# mpc56_mcupower.net
KiCad netlist of a schematic drawn in Altium Designer
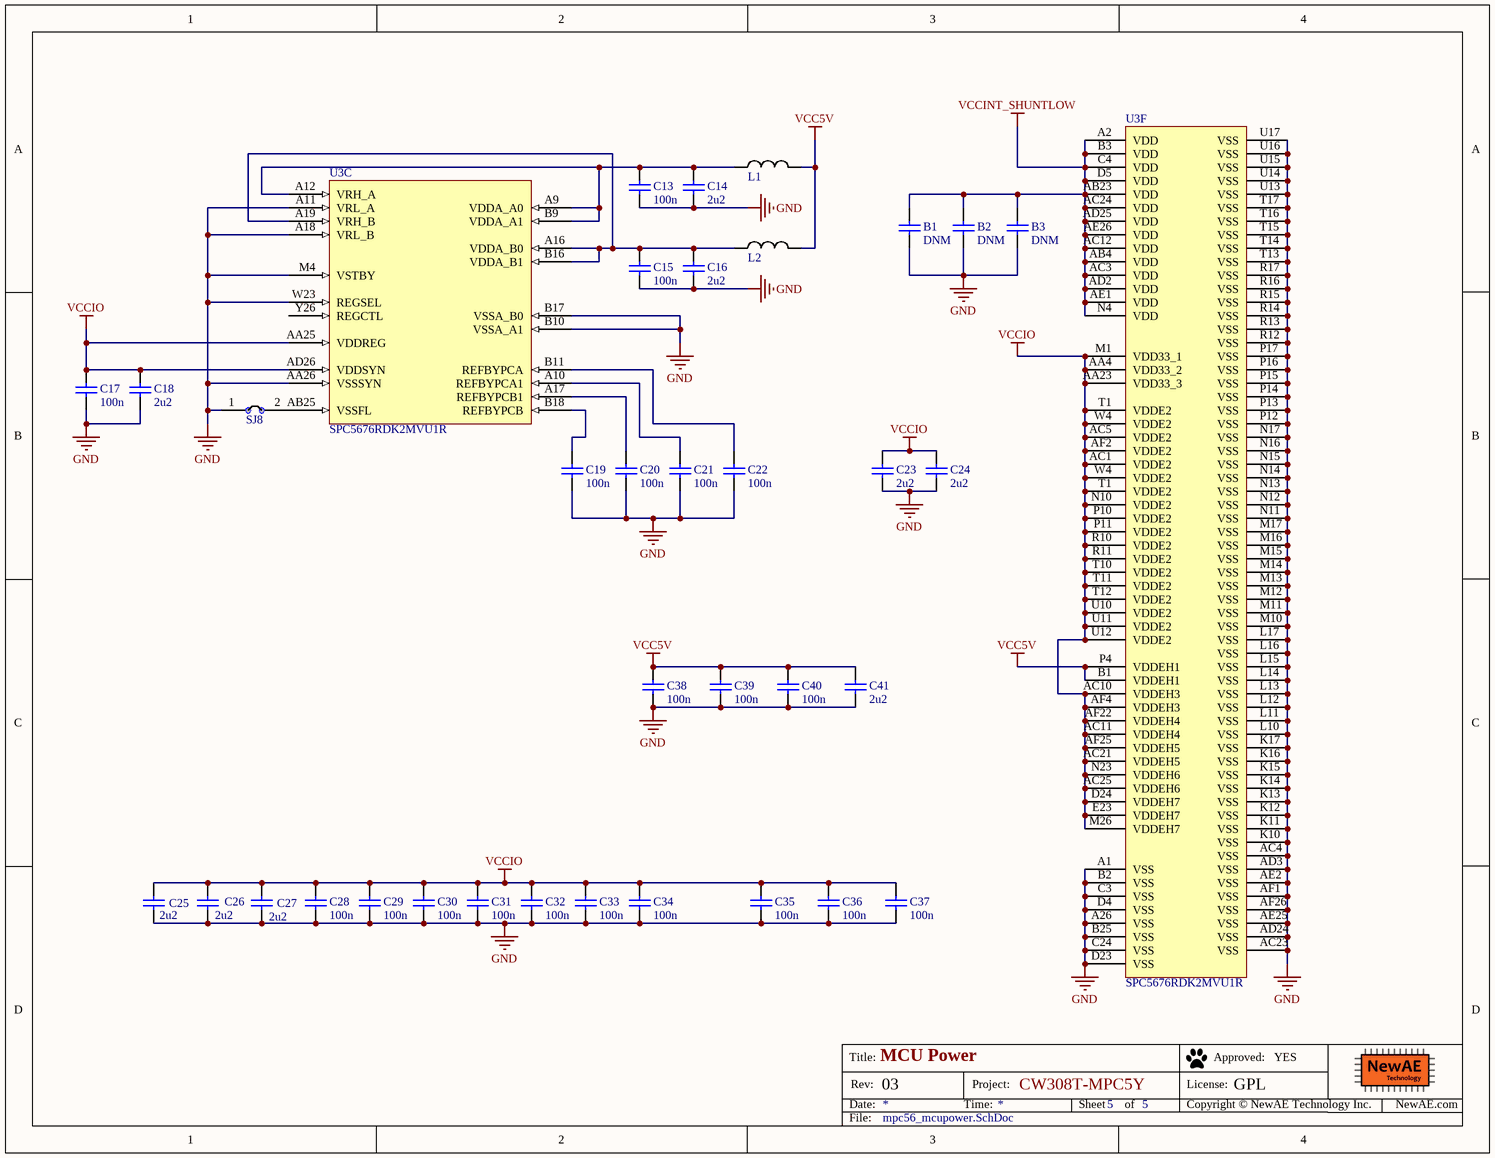
[diagram p0: mpc56_mcupower.SchDoc]

(export (version "E")
  (design (tool "Eeschema 10.0.6"))
  (components
    (comp (ref "B1")
      (value "DNM")
      (footprint "CAPC0402_M")
      (description "DNM, 0402")
      (fields (field (name "PART NUMBER") "CCHIP-DNM-0402"))
      (libsource (lib "NewAE_AltiumLib") (part "CAP"))
    )
    (comp (ref "B2")
      (value "DNM")
      (footprint "CAPC0402_M")
      (description "DNM, 0402")
      (fields (field (name "PART NUMBER") "CCHIP-DNM-0402"))
      (libsource (lib "NewAE_AltiumLib") (part "CAP"))
    )
    (comp (ref "B3")
      (value "DNM")
      (footprint "CAPC0402_M")
      (description "DNM, 0402")
      (fields (field (name "PART NUMBER") "CCHIP-DNM-0402"))
      (libsource (lib "NewAE_AltiumLib") (part "CAP"))
    )
    (comp (ref "C13")
      (value "100n")
      (footprint "CAPC0402_M")
      (description "100n, 0402")
      (fields (field (name "PART NUMBER") "CCHIP-100n-0402"))
      (libsource (lib "NewAE_AltiumLib") (part "CAP"))
    )
    (comp (ref "C14")
      (value "2u2")
      (footprint "CAPC0603_M")
      (description "2u2, 0603")
      (fields (field (name "PART NUMBER") "CCHIP-2u2-0603"))
      (libsource (lib "NewAE_AltiumLib") (part "CAP"))
    )
    (comp (ref "C15")
      (value "100n")
      (footprint "CAPC0402_M")
      (description "100n, 0402")
      (fields (field (name "PART NUMBER") "CCHIP-100n-0402"))
      (libsource (lib "NewAE_AltiumLib") (part "CAP"))
    )
    (comp (ref "C16")
      (value "2u2")
      (footprint "CAPC0603_M")
      (description "2u2, 0603")
      (fields (field (name "PART NUMBER") "CCHIP-2u2-0603"))
      (libsource (lib "NewAE_AltiumLib") (part "CAP"))
    )
    (comp (ref "C17")
      (value "100n")
      (footprint "CAPC0402_M")
      (description "100n, 0402")
      (fields (field (name "PART NUMBER") "CCHIP-100n-0402"))
      (libsource (lib "NewAE_AltiumLib") (part "CAP"))
    )
    (comp (ref "C18")
      (value "2u2")
      (footprint "CAPC0603_M")
      (description "2u2, 0603")
      (fields (field (name "PART NUMBER") "CCHIP-2u2-0603"))
      (libsource (lib "NewAE_AltiumLib") (part "CAP"))
    )
    (comp (ref "C19")
      (value "100n")
      (footprint "CAPC0402_M")
      (description "100n, 0402")
      (fields (field (name "PART NUMBER") "CCHIP-100n-0402"))
      (libsource (lib "NewAE_AltiumLib") (part "CAP"))
    )
    (comp (ref "C20")
      (value "100n")
      (footprint "CAPC0402_M")
      (description "100n, 0402")
      (fields (field (name "PART NUMBER") "CCHIP-100n-0402"))
      (libsource (lib "NewAE_AltiumLib") (part "CAP"))
    )
    (comp (ref "C21")
      (value "100n")
      (footprint "CAPC0402_M")
      (description "100n, 0402")
      (fields (field (name "PART NUMBER") "CCHIP-100n-0402"))
      (libsource (lib "NewAE_AltiumLib") (part "CAP"))
    )
    (comp (ref "C22")
      (value "100n")
      (footprint "CAPC0402_M")
      (description "100n, 0402")
      (fields (field (name "PART NUMBER") "CCHIP-100n-0402"))
      (libsource (lib "NewAE_AltiumLib") (part "CAP"))
    )
    (comp (ref "C23")
      (value "2u2")
      (footprint "CAPC0603_M")
      (description "2u2, 0603")
      (fields (field (name "PART NUMBER") "CCHIP-2u2-0603"))
      (libsource (lib "NewAE_AltiumLib") (part "CAP"))
    )
    (comp (ref "C24")
      (value "2u2")
      (footprint "CAPC0603_M")
      (description "2u2, 0603")
      (fields (field (name "PART NUMBER") "CCHIP-2u2-0603"))
      (libsource (lib "NewAE_AltiumLib") (part "CAP"))
    )
    (comp (ref "C25")
      (value "2u2")
      (footprint "CAPC0603_M")
      (description "2u2, 0603")
      (fields (field (name "PART NUMBER") "CCHIP-2u2-0603"))
      (libsource (lib "NewAE_AltiumLib") (part "CAP"))
    )
    (comp (ref "C26")
      (value "2u2")
      (footprint "CAPC0603_M")
      (description "2u2, 0603")
      (fields (field (name "PART NUMBER") "CCHIP-2u2-0603"))
      (libsource (lib "NewAE_AltiumLib") (part "CAP"))
    )
    (comp (ref "C27")
      (value "2u2")
      (footprint "CAPC0603_M")
      (description "2u2, 0603")
      (fields (field (name "PART NUMBER") "CCHIP-2u2-0603"))
      (libsource (lib "NewAE_AltiumLib") (part "CAP"))
    )
    (comp (ref "C28")
      (value "100n")
      (footprint "CAPC0402_M")
      (description "100n, 0402")
      (fields (field (name "PART NUMBER") "CCHIP-100n-0402"))
      (libsource (lib "NewAE_AltiumLib") (part "CAP"))
    )
    (comp (ref "C29")
      (value "100n")
      (footprint "CAPC0402_M")
      (description "100n, 0402")
      (fields (field (name "PART NUMBER") "CCHIP-100n-0402"))
      (libsource (lib "NewAE_AltiumLib") (part "CAP"))
    )
    (comp (ref "C30")
      (value "100n")
      (footprint "CAPC0402_M")
      (description "100n, 0402")
      (fields (field (name "PART NUMBER") "CCHIP-100n-0402"))
      (libsource (lib "NewAE_AltiumLib") (part "CAP"))
    )
    (comp (ref "C31")
      (value "100n")
      (footprint "CAPC0402_M")
      (description "100n, 0402")
      (fields (field (name "PART NUMBER") "CCHIP-100n-0402"))
      (libsource (lib "NewAE_AltiumLib") (part "CAP"))
    )
    (comp (ref "C32")
      (value "100n")
      (footprint "CAPC0402_M")
      (description "100n, 0402")
      (fields (field (name "PART NUMBER") "CCHIP-100n-0402"))
      (libsource (lib "NewAE_AltiumLib") (part "CAP"))
    )
    (comp (ref "C33")
      (value "100n")
      (footprint "CAPC0402_M")
      (description "100n, 0402")
      (fields (field (name "PART NUMBER") "CCHIP-100n-0402"))
      (libsource (lib "NewAE_AltiumLib") (part "CAP"))
    )
    (comp (ref "C34")
      (value "100n")
      (footprint "CAPC0402_M")
      (description "100n, 0402")
      (fields (field (name "PART NUMBER") "CCHIP-100n-0402"))
      (libsource (lib "NewAE_AltiumLib") (part "CAP"))
    )
    (comp (ref "C35")
      (value "100n")
      (footprint "CAPC0402_M")
      (description "100n, 0402")
      (fields (field (name "PART NUMBER") "CCHIP-100n-0402"))
      (libsource (lib "NewAE_AltiumLib") (part "CAP"))
    )
    (comp (ref "C36")
      (value "100n")
      (footprint "CAPC0402_M")
      (description "100n, 0402")
      (fields (field (name "PART NUMBER") "CCHIP-100n-0402"))
      (libsource (lib "NewAE_AltiumLib") (part "CAP"))
    )
    (comp (ref "C37")
      (value "100n")
      (footprint "CAPC0402_M")
      (description "100n, 0402")
      (fields (field (name "PART NUMBER") "CCHIP-100n-0402"))
      (libsource (lib "NewAE_AltiumLib") (part "CAP"))
    )
    (comp (ref "C38")
      (value "100n")
      (footprint "CAPC0402_M")
      (description "100n, 0402")
      (fields (field (name "PART NUMBER") "CCHIP-100n-0402"))
      (libsource (lib "NewAE_AltiumLib") (part "CAP"))
    )
    (comp (ref "C39")
      (value "100n")
      (footprint "CAPC0402_M")
      (description "100n, 0402")
      (fields (field (name "PART NUMBER") "CCHIP-100n-0402"))
      (libsource (lib "NewAE_AltiumLib") (part "CAP"))
    )
    (comp (ref "C40")
      (value "100n")
      (footprint "CAPC0402_M")
      (description "100n, 0402")
      (fields (field (name "PART NUMBER") "CCHIP-100n-0402"))
      (libsource (lib "NewAE_AltiumLib") (part "CAP"))
    )
    (comp (ref "C41")
      (value "2u2")
      (footprint "CAPC0603_M")
      (description "2u2, 0603")
      (fields (field (name "PART NUMBER") "CCHIP-2u2-0603"))
      (libsource (lib "NewAE_AltiumLib") (part "CAP"))
    )
    (comp (ref "L1")
      (value "1k @ 1Mhz")
      (footprint "IND_0603")
      (description "Ferrite Beads HI CUR CHIP BD 0603 1000OHMS 25%")
      (fields (field (name "PART NUMBER") "FBCHIP-1k-0603"))
      (libsource (lib "NewAE_AltiumLib") (part "IND"))
    )
    (comp (ref "L2")
      (value "1k @ 1Mhz")
      (footprint "IND_0603")
      (description "Ferrite Beads HI CUR CHIP BD 0603 1000OHMS 25%")
      (fields (field (name "PART NUMBER") "FBCHIP-1k-0603"))
      (libsource (lib "NewAE_AltiumLib") (part "IND"))
    )
    (comp (ref "SJ8")
      (value "NC")
      (footprint "SJ_2S_NC")
      (description "Solder Jumper, NC")
      (fields (field (name "PART NUMBER") "SJ_2S"))
      (libsource (lib "NewAE_AltiumLib") (part "SJ_2S"))
    )
    (comp (ref "U3")
      (value "SPC5676RDK2MVU1R")
      (footprint "TEPBGA416_27x27")
      (description "Dual-Core PPC, Automotive")
      (libsource (lib "NewAE_AltiumLib") (part "SPC5676RDK2MVU1R"))
    )
  )
  (nets
    (net (code "1") (name "GND") (class "Default")
      (node (ref "B1") (pin "2") (pinfunction "2_2") (pintype "passive"))
      (node (ref "B2") (pin "2") (pinfunction "2_2") (pintype "passive"))
      (node (ref "B3") (pin "2") (pinfunction "2_2") (pintype "passive"))
      (node (ref "C13") (pin "2") (pinfunction "2_2") (pintype "passive"))
      (node (ref "C14") (pin "2") (pinfunction "2_2") (pintype "passive"))
      (node (ref "C15") (pin "2") (pinfunction "2_2") (pintype "passive"))
      (node (ref "C16") (pin "2") (pinfunction "2_2") (pintype "passive"))
      (node (ref "C17") (pin "2") (pinfunction "2_2") (pintype "passive"))
      (node (ref "C18") (pin "2") (pinfunction "2_2") (pintype "passive"))
      (node (ref "C19") (pin "2") (pinfunction "2_2") (pintype "passive"))
      (node (ref "C20") (pin "2") (pinfunction "2_2") (pintype "passive"))
      (node (ref "C21") (pin "2") (pinfunction "2_2") (pintype "passive"))
      (node (ref "C22") (pin "2") (pinfunction "2_2") (pintype "passive"))
      (node (ref "C23") (pin "2") (pinfunction "2_2") (pintype "passive"))
      (node (ref "C24") (pin "2") (pinfunction "2_2") (pintype "passive"))
      (node (ref "C25") (pin "2") (pinfunction "2_2") (pintype "passive"))
      (node (ref "C26") (pin "2") (pinfunction "2_2") (pintype "passive"))
      (node (ref "C27") (pin "2") (pinfunction "2_2") (pintype "passive"))
      (node (ref "C28") (pin "2") (pinfunction "2_2") (pintype "passive"))
      (node (ref "C29") (pin "2") (pinfunction "2_2") (pintype "passive"))
      (node (ref "C30") (pin "2") (pinfunction "2_2") (pintype "passive"))
      (node (ref "C31") (pin "2") (pinfunction "2_2") (pintype "passive"))
      (node (ref "C32") (pin "2") (pinfunction "2_2") (pintype "passive"))
      (node (ref "C33") (pin "2") (pinfunction "2_2") (pintype "passive"))
      (node (ref "C34") (pin "2") (pinfunction "2_2") (pintype "passive"))
      (node (ref "C35") (pin "2") (pinfunction "2_2") (pintype "passive"))
      (node (ref "C36") (pin "2") (pinfunction "2_2") (pintype "passive"))
      (node (ref "C37") (pin "2") (pinfunction "2_2") (pintype "passive"))
      (node (ref "C38") (pin "2") (pinfunction "2_2") (pintype "passive"))
      (node (ref "C39") (pin "2") (pinfunction "2_2") (pintype "passive"))
      (node (ref "C40") (pin "2") (pinfunction "2_2") (pintype "passive"))
      (node (ref "C41") (pin "2") (pinfunction "2_2") (pintype "passive"))
      (node (ref "SJ8") (pin "1") (pinfunction "1_1") (pintype "passive"))
      (node (ref "U3") (pin "A1") (pinfunction "VSS_A1") (pintype "passive"))
      (node (ref "U3") (pin "A11") (pinfunction "VRL_A_A11") (pintype "input"))
      (node (ref "U3") (pin "A18") (pinfunction "VRL_B_A18") (pintype "input"))
      (node (ref "U3") (pin "A26") (pinfunction "VSS_A26") (pintype "passive"))
      (node (ref "U3") (pin "AA26") (pinfunction "VSSSYN_AA26") (pintype "input"))
      (node (ref "U3") (pin "AC23") (pinfunction "VSS_AC23") (pintype "passive"))
      (node (ref "U3") (pin "AC4") (pinfunction "VSS_AC4") (pintype "passive"))
      (node (ref "U3") (pin "AD24") (pinfunction "VSS_AD24") (pintype "passive"))
      (node (ref "U3") (pin "AD3") (pinfunction "VSS_AD3") (pintype "passive"))
      (node (ref "U3") (pin "AE2") (pinfunction "VSS_AE2") (pintype "passive"))
      (node (ref "U3") (pin "AE25") (pinfunction "VSS_AE25") (pintype "passive"))
      (node (ref "U3") (pin "AF1") (pinfunction "VSS_AF1") (pintype "passive"))
      (node (ref "U3") (pin "AF26") (pinfunction "VSS_AF26") (pintype "passive"))
      (node (ref "U3") (pin "B10") (pinfunction "VSSA_A1_B10") (pintype "input"))
      (node (ref "U3") (pin "B17") (pinfunction "VSSA_B0_B17") (pintype "input"))
      (node (ref "U3") (pin "B2") (pinfunction "VSS_B2") (pintype "passive"))
      (node (ref "U3") (pin "B25") (pinfunction "VSS_B25") (pintype "passive"))
      (node (ref "U3") (pin "C24") (pinfunction "VSS_C24") (pintype "passive"))
      (node (ref "U3") (pin "C3") (pinfunction "VSS_C3") (pintype "passive"))
      (node (ref "U3") (pin "D23") (pinfunction "VSS_D23") (pintype "passive"))
      (node (ref "U3") (pin "D4") (pinfunction "VSS_D4") (pintype "passive"))
      (node (ref "U3") (pin "K10") (pinfunction "VSS_K10") (pintype "passive"))
      (node (ref "U3") (pin "K11") (pinfunction "VSS_K11") (pintype "passive"))
      (node (ref "U3") (pin "K12") (pinfunction "VSS_K12") (pintype "passive"))
      (node (ref "U3") (pin "K13") (pinfunction "VSS_K13") (pintype "passive"))
      (node (ref "U3") (pin "K14") (pinfunction "VSS_K14") (pintype "passive"))
      (node (ref "U3") (pin "K15") (pinfunction "VSS_K15") (pintype "passive"))
      (node (ref "U3") (pin "K16") (pinfunction "VSS_K16") (pintype "passive"))
      (node (ref "U3") (pin "K17") (pinfunction "VSS_K17") (pintype "passive"))
      (node (ref "U3") (pin "L10") (pinfunction "VSS_L10") (pintype "passive"))
      (node (ref "U3") (pin "L11") (pinfunction "VSS_L11") (pintype "passive"))
      (node (ref "U3") (pin "L12") (pinfunction "VSS_L12") (pintype "passive"))
      (node (ref "U3") (pin "L13") (pinfunction "VSS_L13") (pintype "passive"))
      (node (ref "U3") (pin "L14") (pinfunction "VSS_L14") (pintype "passive"))
      (node (ref "U3") (pin "L15") (pinfunction "VSS_L15") (pintype "passive"))
      (node (ref "U3") (pin "L16") (pinfunction "VSS_L16") (pintype "passive"))
      (node (ref "U3") (pin "L17") (pinfunction "VSS_L17") (pintype "passive"))
      (node (ref "U3") (pin "M10") (pinfunction "VSS_M10") (pintype "passive"))
      (node (ref "U3") (pin "M11") (pinfunction "VSS_M11") (pintype "passive"))
      (node (ref "U3") (pin "M12") (pinfunction "VSS_M12") (pintype "passive"))
      (node (ref "U3") (pin "M13") (pinfunction "VSS_M13") (pintype "passive"))
      (node (ref "U3") (pin "M14") (pinfunction "VSS_M14") (pintype "passive"))
      (node (ref "U3") (pin "M15") (pinfunction "VSS_M15") (pintype "passive"))
      (node (ref "U3") (pin "M16") (pinfunction "VSS_M16") (pintype "passive"))
      (node (ref "U3") (pin "M17") (pinfunction "VSS_M17") (pintype "passive"))
      (node (ref "U3") (pin "M4") (pinfunction "VSTBY_M4") (pintype "input"))
      (node (ref "U3") (pin "N11") (pinfunction "VSS_N11") (pintype "passive"))
      (node (ref "U3") (pin "N12") (pinfunction "VSS_N12") (pintype "passive"))
      (node (ref "U3") (pin "N13") (pinfunction "VSS_N13") (pintype "passive"))
      (node (ref "U3") (pin "N14") (pinfunction "VSS_N14") (pintype "passive"))
      (node (ref "U3") (pin "N15") (pinfunction "VSS_N15") (pintype "passive"))
      (node (ref "U3") (pin "N16") (pinfunction "VSS_N16") (pintype "passive"))
      (node (ref "U3") (pin "N17") (pinfunction "VSS_N17") (pintype "passive"))
      (node (ref "U3") (pin "P12") (pinfunction "VSS_P12") (pintype "passive"))
      (node (ref "U3") (pin "P13") (pinfunction "VSS_P13") (pintype "passive"))
      (node (ref "U3") (pin "P14") (pinfunction "VSS_P14") (pintype "passive"))
      (node (ref "U3") (pin "P15") (pinfunction "VSS_P15") (pintype "passive"))
      (node (ref "U3") (pin "P16") (pinfunction "VSS_P16") (pintype "passive"))
      (node (ref "U3") (pin "P17") (pinfunction "VSS_P17") (pintype "passive"))
      (node (ref "U3") (pin "R12") (pinfunction "VSS_R12") (pintype "passive"))
      (node (ref "U3") (pin "R13") (pinfunction "VSS_R13") (pintype "passive"))
      (node (ref "U3") (pin "R14") (pinfunction "VSS_R14") (pintype "passive"))
      (node (ref "U3") (pin "R15") (pinfunction "VSS_R15") (pintype "passive"))
      (node (ref "U3") (pin "R16") (pinfunction "VSS_R16") (pintype "passive"))
      (node (ref "U3") (pin "R17") (pinfunction "VSS_R17") (pintype "passive"))
      (node (ref "U3") (pin "T13") (pinfunction "VSS_T13") (pintype "passive"))
      (node (ref "U3") (pin "T14") (pinfunction "VSS_T14") (pintype "passive"))
      (node (ref "U3") (pin "T15") (pinfunction "VSS_T15") (pintype "passive"))
      (node (ref "U3") (pin "T16") (pinfunction "VSS_T16") (pintype "passive"))
      (node (ref "U3") (pin "T17") (pinfunction "VSS_T17") (pintype "passive"))
      (node (ref "U3") (pin "U13") (pinfunction "VSS_U13") (pintype "passive"))
      (node (ref "U3") (pin "U14") (pinfunction "VSS_U14") (pintype "passive"))
      (node (ref "U3") (pin "U15") (pinfunction "VSS_U15") (pintype "passive"))
      (node (ref "U3") (pin "U16") (pinfunction "VSS_U16") (pintype "passive"))
      (node (ref "U3") (pin "U17") (pinfunction "VSS_U17") (pintype "passive"))
      (node (ref "U3") (pin "W23") (pinfunction "REGSEL_W23") (pintype "input"))
    )
    (net (code "2") (name "Net-(U3C-REFBYPCA)") (class "Default")
      (node (ref "C22") (pin "1") (pinfunction "1_1") (pintype "passive"))
      (node (ref "U3") (pin "B11") (pinfunction "REFBYPCA_B11") (pintype "input"))
    )
    (net (code "3") (name "Net-(U3C-REFBYPCA1)") (class "Default")
      (node (ref "C21") (pin "1") (pinfunction "1_1") (pintype "passive"))
      (node (ref "U3") (pin "A10") (pinfunction "REFBYPCA1_A10") (pintype "input"))
    )
    (net (code "4") (name "Net-(U3C-REFBYPCB)") (class "Default")
      (node (ref "C19") (pin "1") (pinfunction "1_1") (pintype "passive"))
      (node (ref "U3") (pin "B18") (pinfunction "REFBYPCB_B18") (pintype "input"))
    )
    (net (code "5") (name "Net-(U3C-REFBYPCB1)") (class "Default")
      (node (ref "C20") (pin "1") (pinfunction "1_1") (pintype "passive"))
      (node (ref "U3") (pin "A17") (pinfunction "REFBYPCB1_A17") (pintype "input"))
    )
    (net (code "6") (name "Net-(U3C-VDDA_A0)") (class "Default")
      (node (ref "C13") (pin "1") (pinfunction "1_1") (pintype "passive"))
      (node (ref "C14") (pin "1") (pinfunction "1_1") (pintype "passive"))
      (node (ref "L1") (pin "1") (pinfunction "1_1") (pintype "passive"))
      (node (ref "U3") (pin "A12") (pinfunction "VRH_A_A12") (pintype "input"))
      (node (ref "U3") (pin "A9") (pinfunction "VDDA_A0_A9") (pintype "input"))
      (node (ref "U3") (pin "B9") (pinfunction "VDDA_A1_B9") (pintype "input"))
    )
    (net (code "7") (name "Net-(U3C-VDDA_B0)") (class "Default")
      (node (ref "C15") (pin "1") (pinfunction "1_1") (pintype "passive"))
      (node (ref "C16") (pin "1") (pinfunction "1_1") (pintype "passive"))
      (node (ref "L2") (pin "1") (pinfunction "1_1") (pintype "passive"))
      (node (ref "U3") (pin "A16") (pinfunction "VDDA_B0_A16") (pintype "input"))
      (node (ref "U3") (pin "A19") (pinfunction "VRH_B_A19") (pintype "input"))
      (node (ref "U3") (pin "B16") (pinfunction "VDDA_B1_B16") (pintype "input"))
    )
    (net (code "8") (name "Net-(U3C-VSSFL)") (class "Default")
      (node (ref "SJ8") (pin "2") (pinfunction "2_2") (pintype "passive"))
      (node (ref "U3") (pin "AB25") (pinfunction "VSSFL_AB25") (pintype "input"))
    )
    (net (code "9") (name "VCC5V") (class "Default")
      (node (ref "C38") (pin "1") (pinfunction "1_1") (pintype "passive"))
      (node (ref "C39") (pin "1") (pinfunction "1_1") (pintype "passive"))
      (node (ref "C40") (pin "1") (pinfunction "1_1") (pintype "passive"))
      (node (ref "C41") (pin "1") (pinfunction "1_1") (pintype "passive"))
      (node (ref "L1") (pin "2") (pinfunction "2_2") (pintype "passive"))
      (node (ref "L2") (pin "2") (pinfunction "2_2") (pintype "passive"))
      (node (ref "U3") (pin "B1") (pinfunction "VDDEH1_B1") (pintype "passive"))
      (node (ref "U3") (pin "P4") (pinfunction "VDDEH1_P4") (pintype "passive"))
    )
    (net (code "10") (name "VCCINT_SHUNTLOW") (class "Default")
      (node (ref "B1") (pin "1") (pinfunction "1_1") (pintype "passive"))
      (node (ref "B2") (pin "1") (pinfunction "1_1") (pintype "passive"))
      (node (ref "B3") (pin "1") (pinfunction "1_1") (pintype "passive"))
      (node (ref "U3") (pin "A2") (pinfunction "VDD_A2") (pintype "passive"))
      (node (ref "U3") (pin "AB23") (pinfunction "VDD_AB23") (pintype "passive"))
      (node (ref "U3") (pin "AB4") (pinfunction "VDD_AB4") (pintype "passive"))
      (node (ref "U3") (pin "AC12") (pinfunction "VDD_AC12") (pintype "passive"))
      (node (ref "U3") (pin "AC24") (pinfunction "VDD_AC24") (pintype "passive"))
      (node (ref "U3") (pin "AC3") (pinfunction "VDD_AC3") (pintype "passive"))
      (node (ref "U3") (pin "AD2") (pinfunction "VDD_AD2") (pintype "passive"))
      (node (ref "U3") (pin "AD25") (pinfunction "VDD_AD25") (pintype "passive"))
      (node (ref "U3") (pin "AE1") (pinfunction "VDD_AE1") (pintype "passive"))
      (node (ref "U3") (pin "AE26") (pinfunction "VDD_AE26") (pintype "passive"))
      (node (ref "U3") (pin "B3") (pinfunction "VDD_B3") (pintype "passive"))
      (node (ref "U3") (pin "C4") (pinfunction "VDD_C4") (pintype "passive"))
      (node (ref "U3") (pin "D5") (pinfunction "VDD_D5") (pintype "passive"))
      (node (ref "U3") (pin "N4") (pinfunction "VDD_N4") (pintype "passive"))
    )
    (net (code "11") (name "VCCIO") (class "Default")
      (node (ref "C17") (pin "1") (pinfunction "1_1") (pintype "passive"))
      (node (ref "C18") (pin "1") (pinfunction "1_1") (pintype "passive"))
      (node (ref "C23") (pin "1") (pinfunction "1_1") (pintype "passive"))
      (node (ref "C24") (pin "1") (pinfunction "1_1") (pintype "passive"))
      (node (ref "C25") (pin "1") (pinfunction "1_1") (pintype "passive"))
      (node (ref "C26") (pin "1") (pinfunction "1_1") (pintype "passive"))
      (node (ref "C27") (pin "1") (pinfunction "1_1") (pintype "passive"))
      (node (ref "C28") (pin "1") (pinfunction "1_1") (pintype "passive"))
      (node (ref "C29") (pin "1") (pinfunction "1_1") (pintype "passive"))
      (node (ref "C30") (pin "1") (pinfunction "1_1") (pintype "passive"))
      (node (ref "C31") (pin "1") (pinfunction "1_1") (pintype "passive"))
      (node (ref "C32") (pin "1") (pinfunction "1_1") (pintype "passive"))
      (node (ref "C33") (pin "1") (pinfunction "1_1") (pintype "passive"))
      (node (ref "C34") (pin "1") (pinfunction "1_1") (pintype "passive"))
      (node (ref "C35") (pin "1") (pinfunction "1_1") (pintype "passive"))
      (node (ref "C36") (pin "1") (pinfunction "1_1") (pintype "passive"))
      (node (ref "C37") (pin "1") (pinfunction "1_1") (pintype "passive"))
      (node (ref "U3") (pin "AA23") (pinfunction "VDD33_3_AA23") (pintype "passive"))
      (node (ref "U3") (pin "AA25") (pinfunction "VDDREG_AA25") (pintype "input"))
      (node (ref "U3") (pin "AA4") (pinfunction "VDD33_2_AA4") (pintype "passive"))
      (node (ref "U3") (pin "AC1") (pinfunction "VDDE2_AC1") (pintype "passive"))
      (node (ref "U3") (pin "AC10") (pinfunction "VDDEH3_AC10") (pintype "passive"))
      (node (ref "U3") (pin "AC11") (pinfunction "VDDEH4_AC11") (pintype "passive"))
      (node (ref "U3") (pin "AC21") (pinfunction "VDDEH5_AC21") (pintype "passive"))
      (node (ref "U3") (pin "AC25") (pinfunction "VDDEH6_AC25") (pintype "passive"))
      (node (ref "U3") (pin "AC5") (pinfunction "VDDE2_AC5") (pintype "passive"))
      (node (ref "U3") (pin "AD26") (pinfunction "VDDSYN_AD26") (pintype "input"))
      (node (ref "U3") (pin "AF2") (pinfunction "VDDE2_AF2") (pintype "passive"))
      (node (ref "U3") (pin "AF22") (pinfunction "VDDEH4_AF22") (pintype "passive"))
      (node (ref "U3") (pin "AF25") (pinfunction "VDDEH5_AF25") (pintype "passive"))
      (node (ref "U3") (pin "AF4") (pinfunction "VDDEH3_AF4") (pintype "passive"))
      (node (ref "U3") (pin "D24") (pinfunction "VDDEH7_D24") (pintype "passive"))
      (node (ref "U3") (pin "E23") (pinfunction "VDDEH7_E23") (pintype "passive"))
      (node (ref "U3") (pin "M1") (pinfunction "VDD33_1_M1") (pintype "passive"))
      (node (ref "U3") (pin "M26") (pinfunction "VDDEH7_M26") (pintype "passive"))
      (node (ref "U3") (pin "N10") (pinfunction "VDDE2_N10") (pintype "passive"))
      (node (ref "U3") (pin "N23") (pinfunction "VDDEH6_N23") (pintype "passive"))
      (node (ref "U3") (pin "P10") (pinfunction "VDDE2_P10") (pintype "passive"))
      (node (ref "U3") (pin "P11") (pinfunction "VDDE2_P11") (pintype "passive"))
      (node (ref "U3") (pin "R10") (pinfunction "VDDE2_R10") (pintype "passive"))
      (node (ref "U3") (pin "R11") (pinfunction "VDDE2_R11") (pintype "passive"))
      (node (ref "U3") (pin "T1") (pinfunction "VDDE2_T1") (pintype "passive"))
      (node (ref "U3") (pin "T10") (pinfunction "VDDE2_T10") (pintype "passive"))
      (node (ref "U3") (pin "T11") (pinfunction "VDDE2_T11") (pintype "passive"))
      (node (ref "U3") (pin "T12") (pinfunction "VDDE2_T12") (pintype "passive"))
      (node (ref "U3") (pin "U10") (pinfunction "VDDE2_U10") (pintype "passive"))
      (node (ref "U3") (pin "U11") (pinfunction "VDDE2_U11") (pintype "passive"))
      (node (ref "U3") (pin "U12") (pinfunction "VDDE2_U12") (pintype "passive"))
      (node (ref "U3") (pin "W4") (pinfunction "VDDE2_W4") (pintype "passive"))
    )
    (net (code "12") (name "unconnected-(U3C-REGCTL-PadY26)") (class "Default")
      (node (ref "U3") (pin "Y26") (pinfunction "REGCTL_Y26") (pintype "input"))
    )
  )
)
